# Node_Schematic_V2.net
KiCad netlist of a schematic drawn in Altium Designer
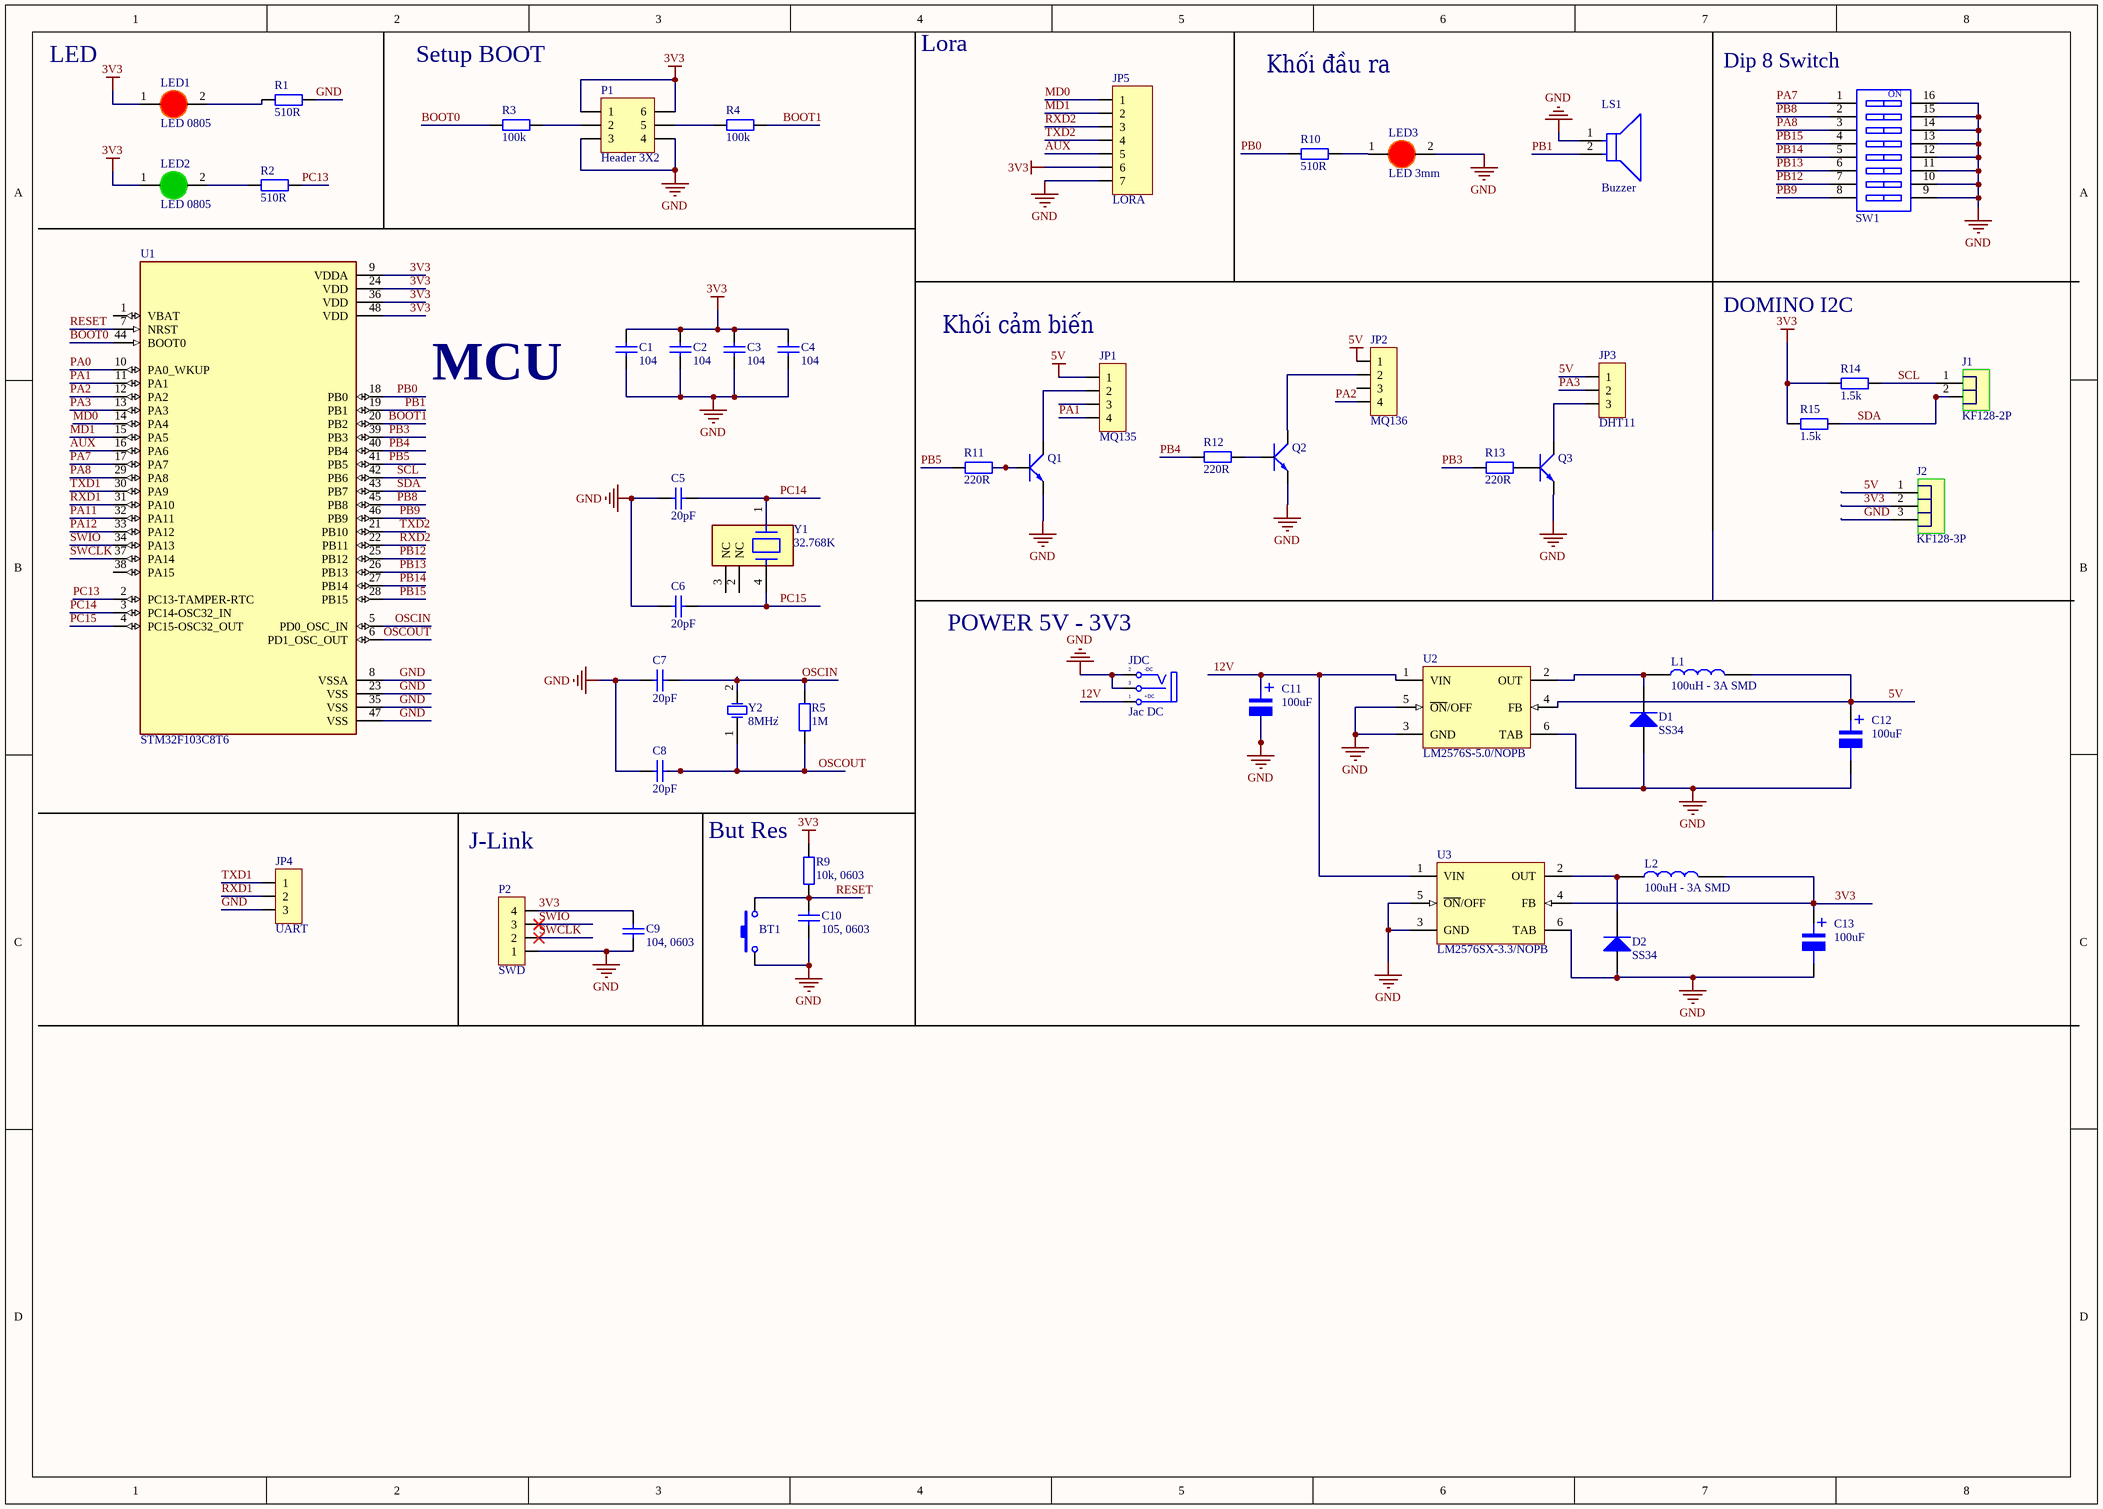
[diagram p0: Node_Schematic_V2.SchDoc]

(export (version "E")
  (design (tool "Eeschema 10.0.6"))
  (components
    (comp (ref "BT1")
      (value "Nut Nhan 2 Chan SMD 3x6x2.5")
      (footprint "Nut Nhan 2 Chan SMD 3x6x2.5")
      (libsource (lib "Altium_Lib_by_KhueNguyenCreator") (part "Nut Nhan 2 Chan SMD 3x6x2.5"))
    )
    (comp (ref "C1")
      (value "104")
      (footprint "tu 0603")
      (description "Dán")
      (libsource (lib "Altium_Lib_by_KhueNguyenCreator") (part "Tu 0603 104 50V 10%"))
    )
    (comp (ref "C2")
      (value "104")
      (footprint "tu 0603")
      (description "Dán")
      (libsource (lib "Altium_Lib_by_KhueNguyenCreator") (part "Tu 0603 104 50V 10%"))
    )
    (comp (ref "C3")
      (value "104")
      (footprint "tu 0603")
      (description "Dán")
      (libsource (lib "Altium_Lib_by_KhueNguyenCreator") (part "Tu 0603 104 50V 10%"))
    )
    (comp (ref "C4")
      (value "104")
      (footprint "tu 0603")
      (description "Dán")
      (libsource (lib "Altium_Lib_by_KhueNguyenCreator") (part "Tu 0603 104 50V 10%"))
    )
    (comp (ref "C5")
      (value "20pF")
      (footprint "tu 0805")
      (description "Dán")
      (libsource (lib "Altium_Lib_by_KhueNguyenCreator") (part "Tu 0805 20pF 50V 10%"))
    )
    (comp (ref "C6")
      (value "20pF")
      (footprint "tu 0805")
      (description "Dán")
      (libsource (lib "Altium_Lib_by_KhueNguyenCreator") (part "Tu 0805 20pF 50V 10%"))
    )
    (comp (ref "C7")
      (value "20pF")
      (footprint "tu 0805")
      (description "Dán")
      (libsource (lib "Altium_Lib_by_KhueNguyenCreator") (part "Tu 0805 20pF 50V 10%"))
    )
    (comp (ref "C8")
      (value "20pF")
      (footprint "tu 0805")
      (description "Dán")
      (libsource (lib "Altium_Lib_by_KhueNguyenCreator") (part "Tu 0805 20pF 50V 10%"))
    )
    (comp (ref "C9")
      (value "104, 0603")
      (footprint "tu 0603")
      (description "Dán")
      (libsource (lib "Altium_Lib_by_KhueNguyenCreator") (part "Tu 0603 104 50V 10%"))
    )
    (comp (ref "C10")
      (value "105, 0603")
      (footprint "tu 0603")
      (description "Dán")
      (libsource (lib "Altium_Lib_by_KhueNguyenCreator") (part "Tu 0603 105 16V 20%"))
    )
    (comp (ref "C11")
      (value "100uF")
      (footprint "tu nhom 8 (f)")
      (description "Dán")
      (libsource (lib "Altium_Lib_by_KhueNguyenCreator") (part "Tu Nhom 100uF 50V"))
    )
    (comp (ref "C12")
      (value "100uF")
      (footprint "tu nhom 8 (f)")
      (description "Dán")
      (libsource (lib "Altium_Lib_by_KhueNguyenCreator") (part "Tu Nhom 100uF 50V"))
    )
    (comp (ref "C13")
      (value "100uF")
      (footprint "tu nhom 8 (f)")
      (description "Dán")
      (libsource (lib "Altium_Lib_by_KhueNguyenCreator") (part "Tu Nhom 100uF 50V"))
    )
    (comp (ref "D1")
      (value "SS34")
      (footprint "DIODE SMA")
      (description "Dán")
      (libsource (lib "Altium_Lib_by_KhueNguyenCreator") (part "Diode SS34 ( 1N5822 )"))
    )
    (comp (ref "D2")
      (value "SS34")
      (footprint "DIODE SMA")
      (description "Dán")
      (libsource (lib "Altium_Lib_by_KhueNguyenCreator") (part "Diode SS34 ( 1N5822 )"))
    )
    (comp (ref "J1")
      (value "KF128-2P")
      (footprint "KF128-5.08-2P")
      (libsource (lib "KF128") (part "KF128-2P"))
    )
    (comp (ref "J2")
      (value "KF128-3P")
      (footprint "KF128-5.08-3P")
      (libsource (lib "KF128") (part "KF128-3P"))
    )
    (comp (ref "JDC")
      (value "Jac DC")
      (footprint "DC-IN")
      (description "Jac DC input")
      (libsource (lib "syhaunguyen") (part "DCIN"))
    )
    (comp (ref "JP1")
      (value "MQ135")
      (footprint "JP 1x4 CT")
      (description "Cắm")
      (libsource (lib "Altium_Lib_by_KhueNguyenCreator") (part "JP 1x4 2.54 Cai Thang"))
    )
    (comp (ref "JP2")
      (value "MQ136")
      (footprint "JP 1x4 CT")
      (description "Cắm")
      (libsource (lib "Altium_Lib_by_KhueNguyenCreator") (part "JP 1x4 2.54 Cai Thang"))
    )
    (comp (ref "JP3")
      (value "DHT11")
      (footprint "JP 1x3 CT")
      (description "Cắm")
      (libsource (lib "Altium_Lib_by_KhueNguyenCreator") (part "JP 1x3 2.54 Cai Thang"))
    )
    (comp (ref "JP4")
      (value "UART")
      (footprint "JP 1x3 DT")
      (description "Cắm")
      (libsource (lib "Altium_Lib_by_KhueNguyenCreator") (part "JP 1x3 2.54 Duc Thang"))
    )
    (comp (ref "JP5")
      (value "LORA")
      (footprint "JP 1x7 CT")
      (description "Cắm")
      (libsource (lib "Altium_Lib_by_KhueNguyenCreator") (part "JP 1x7 2.54 Cai Thang"))
    )
    (comp (ref "L1")
      (value "100uH - 3A SMD")
      (footprint "Cuon Cam 12x12x10")
      (description "Dán")
      (libsource (lib "Altium_Lib_by_KhueNguyenCreator") (part "CUON CAM 100uH SMD"))
    )
    (comp (ref "L2")
      (value "100uH - 3A SMD")
      (footprint "Cuon Cam 12x12x10")
      (description "Dán")
      (libsource (lib "Altium_Lib_by_KhueNguyenCreator") (part "CUON CAM 100uH SMD"))
    )
    (comp (ref "LED1")
      (value "LED 0805")
      (footprint "LED-0805-Red")
      (description "Dán")
      (libsource (lib "Altium_Lib_by_KhueNguyenCreator") (part "LED 0805 Do"))
    )
    (comp (ref "LED2")
      (value "LED 0805")
      (footprint "LED-0805-Green")
      (description "Dán")
      (libsource (lib "Altium_Lib_by_KhueNguyenCreator") (part "LED 0805 Xanh La"))
    )
    (comp (ref "LED3")
      (value "LED 3mm")
      (footprint "LED-3MM-RED")
      (description "Cắm")
      (libsource (lib "Altium_Lib_by_KhueNguyenCreator") (part "LED 3mm Do"))
    )
    (comp (ref "LS1")
      (value "Buzzer")
      (footprint "FP-MCKPX-G1203A-K4056-MFG")
      (description "MAGNETIC BUZZER AND TRANSDUCER - More Details")
      (fields
        (field (name "MANUFACTURER PART NUMBER") "MCKPX-G1203A-K4056")
        (field (name "MANUFACTURER") "Multicomp Pro")
      )
      (libsource (lib "Altium Content Vault") (part "1973c4b650225fd2ddacaff6b763965"))
    )
    (comp (ref "P1")
      (value "Header 3X2")
      (footprint "JP 2x3 DT")
      (description "Cắm")
      (libsource (lib "Altium_Lib_by_KhueNguyenCreator") (part "JP 2x3 2.54 Duc Thang"))
    )
    (comp (ref "P2")
      (value "SWD")
      (footprint "JP 1x4 DT")
      (description "Cắm")
      (libsource (lib "Altium_Lib_by_KhueNguyenCreator") (part "JP 1x4 2.54 Duc Thang"))
    )
    (comp (ref "Q1")
      (value "?")
      (footprint "TO92")
      (description "NPN transistor EBC")
      (libsource (lib "Altium_Lib_by_KhueNguyenCreator") (part "Trans 2N3904"))
    )
    (comp (ref "Q2")
      (value "?")
      (footprint "TO92")
      (description "NPN transistor EBC")
      (libsource (lib "Altium_Lib_by_KhueNguyenCreator") (part "Trans 2N3904"))
    )
    (comp (ref "Q3")
      (value "?")
      (footprint "TO92")
      (description "NPN transistor EBC")
      (libsource (lib "Altium_Lib_by_KhueNguyenCreator") (part "Trans 2N3904"))
    )
    (comp (ref "R1")
      (value "510R")
      (footprint "tro smd 0603")
      (description "Dán")
      (libsource (lib "Altium_Lib_by_KhueNguyenCreator") (part "Tro 0603 5% 510R"))
    )
    (comp (ref "R2")
      (value "510R")
      (footprint "tro smd 0603")
      (description "Dán")
      (libsource (lib "Altium_Lib_by_KhueNguyenCreator") (part "Tro 0603 5% 510R"))
    )
    (comp (ref "R3")
      (value "100k")
      (footprint "tro smd 0603")
      (description "Dán")
      (libsource (lib "Altium_Lib_by_KhueNguyenCreator") (part "Tro 0603 5% 100k"))
    )
    (comp (ref "R4")
      (value "100k")
      (footprint "tro smd 0603")
      (description "Dán")
      (libsource (lib "Altium_Lib_by_KhueNguyenCreator") (part "Tro 0603 5% 100k"))
    )
    (comp (ref "R5")
      (value "1M")
      (footprint "tro smd 0603")
      (description "Dán")
      (libsource (lib "Altium_Lib_by_KhueNguyenCreator") (part "Tro 0603 5% 1M"))
    )
    (comp (ref "R9")
      (value "10k, 0603")
      (footprint "tro smd 0603")
      (description "Dán")
      (libsource (lib "Altium_Lib_by_KhueNguyenCreator") (part "Tro 0603 1% 10k"))
    )
    (comp (ref "R10")
      (value "510R")
      (footprint "tro smd 0603")
      (description "Dán")
      (libsource (lib "Altium_Lib_by_KhueNguyenCreator") (part "Tro 0603 5% 510R"))
    )
    (comp (ref "R11")
      (value "220R")
      (footprint "tro smd 0603")
      (description "Dán")
      (libsource (lib "Altium_Lib_by_KhueNguyenCreator") (part "Tro 0603 5% 220R"))
    )
    (comp (ref "R12")
      (value "220R")
      (footprint "tro smd 0603")
      (description "Dán")
      (libsource (lib "Altium_Lib_by_KhueNguyenCreator") (part "Tro 0603 5% 220R"))
    )
    (comp (ref "R13")
      (value "220R")
      (footprint "tro smd 0603")
      (description "Dán")
      (libsource (lib "Altium_Lib_by_KhueNguyenCreator") (part "Tro 0603 5% 220R"))
    )
    (comp (ref "R14")
      (value "1.5k")
      (footprint "tro smd 0603")
      (description "Dán")
      (libsource (lib "Altium_Lib_by_KhueNguyenCreator") (part "Tro 0603 5% 1.5k"))
    )
    (comp (ref "R15")
      (value "1.5k")
      (footprint "tro smd 0603")
      (description "Dán")
      (libsource (lib "Altium_Lib_by_KhueNguyenCreator") (part "Tro 0603 5% 1.5k"))
    )
    (comp (ref "SW1")
      (value "418117270908")
      (footprint "418117270908")
      (description "WS-DITV Compact THT Dip Switch, Raised Actuator, pitch 2.54mm, 8p")
      (fields (field (name "MANUFACTURER") "Wurth Elektronik"))
      (libsource (lib "Dip8Switch") (part "418117270908"))
    )
    (comp (ref "U1")
      (value "STM32F103C8T6")
      (footprint "QFP50P900X900X160-48N")
      (description "ARM® Cortex®-M3 STM32F1 Microcontroller IC 32-Bit 72MHz 64KB (64K x 8) FLASH 48-LQFP (7x7)")
      (fields (field (name "MF") "STMicroelectronics"))
      (libsource (lib "STM32F103C8T6") (part "STM32F103C8T6"))
    )
    (comp (ref "U2")
      (value "LM2576S-5.0/NOPB")
      (footprint "KTT0005B_N")
      (description "SIMPLE SWITCHER® 3A Step-Down Voltage Regulator, 5-pin TO-263, Pb-Free")
      (fields (field (name "MANUFACTURER") "Texas Instruments"))
      (libsource (lib "LM2576S5NOPB") (part "CMP-0069-00114-3"))
    )
    (comp (ref "U3")
      (value "LM2576SX-3.3/NOPB")
      (footprint "KTT0005B_L")
      (description "SIMPLE SWITCHER® 3A Step-Down Voltage Regulator, 5-pin TO-263, Pb-Free")
      (fields (field (name "MANUFACTURER") "Texas Instruments"))
      (libsource (lib "Altium Content Vault") (part "PM-REG-LM2575HVS-12"))
    )
    (comp (ref "Y1")
      (value "32.768K")
      (footprint "FP-ABS25-MFG")
      (description "CRYSTAL 32.7680KHZ 12.5PF SMD")
      (fields (field (name "TOLERANCE") "20ppm"))
      (libsource (lib "thachanh_36,768k") (part "CMP-2000-05037-2"))
    )
    (comp (ref "Y2")
      (value "8MHz")
      (footprint "ABRA-ABLS-14.7456MHZ-B2-T_V")
      (description "Low Profile Crystal, 8.0 MHz, +/- 30 ppm, -20 to 70 degC, 2-Pin SMD, RoHS, Tape and Reel")
      (fields (field (name "MANUFACTURER") "ABRACON") (field (name "TOLERANCE") "30PPM"))
      (libsource (lib "thachanh_8M") (part "CMP-2000-05726-1"))
    )
  )
  (nets
    (net (code "1") (name "/12V") (class "Default")
      (node (ref "C11") (pin "1") (pinfunction "1_1") (pintype "passive"))
      (node (ref "JDC") (pin "1") (pinfunction "T_1") (pintype "passive"))
      (node (ref "U2") (pin "1") (pinfunction "VIN_1") (pintype "power_in"))
      (node (ref "U3") (pin "1") (pinfunction "VIN_1") (pintype "power_in"))
    )
    (net (code "2") (name "/AUX") (class "Default")
      (node (ref "JP5") (pin "5") (pinfunction "5_5") (pintype "passive"))
      (node (ref "U1") (pin "16") (pinfunction "PA6_16") (pintype "bidirectional"))
    )
    (net (code "3") (name "/BOOT0") (class "Default")
      (node (ref "R3") (pin "1") (pinfunction "1_1") (pintype "passive"))
      (node (ref "U1") (pin "44") (pinfunction "BOOT0_44") (pintype "input"))
    )
    (net (code "4") (name "/BOOT1") (class "Default")
      (node (ref "R4") (pin "2") (pinfunction "2_2") (pintype "passive"))
      (node (ref "U1") (pin "20") (pinfunction "PB2_20") (pintype "bidirectional"))
    )
    (net (code "5") (name "/MD0") (class "Default")
      (node (ref "JP5") (pin "1") (pinfunction "1_1") (pintype "passive"))
      (node (ref "U1") (pin "14") (pinfunction "PA4_14") (pintype "bidirectional"))
    )
    (net (code "6") (name "/MD1") (class "Default")
      (node (ref "JP5") (pin "2") (pinfunction "2_2") (pintype "passive"))
      (node (ref "U1") (pin "15") (pinfunction "PA5_15") (pintype "bidirectional"))
    )
    (net (code "7") (name "/OSCIN") (class "Default")
      (node (ref "C7") (pin "1") (pinfunction "1_1") (pintype "passive"))
      (node (ref "R5") (pin "2") (pinfunction "2_2") (pintype "passive"))
      (node (ref "U1") (pin "5") (pinfunction "PD0_OSC_IN_5") (pintype "bidirectional"))
      (node (ref "Y2") (pin "2") (pinfunction "X2_2") (pintype "passive"))
    )
    (net (code "8") (name "/OSCOUT") (class "Default")
      (node (ref "C8") (pin "1") (pinfunction "1_1") (pintype "passive"))
      (node (ref "R5") (pin "1") (pinfunction "1_1") (pintype "passive"))
      (node (ref "U1") (pin "6") (pinfunction "PD1_OSC_OUT_6") (pintype "bidirectional"))
      (node (ref "Y2") (pin "1") (pinfunction "X1_1") (pintype "passive"))
    )
    (net (code "9") (name "/PA0") (class "Default")
      (node (ref "U1") (pin "10") (pinfunction "PA0_WKUP_10") (pintype "bidirectional"))
    )
    (net (code "10") (name "/PA1") (class "Default")
      (node (ref "JP1") (pin "4") (pinfunction "4_4") (pintype "passive"))
      (node (ref "U1") (pin "11") (pinfunction "PA1_11") (pintype "bidirectional"))
    )
    (net (code "11") (name "/PA2") (class "Default")
      (node (ref "JP2") (pin "4") (pinfunction "4_4") (pintype "passive"))
      (node (ref "U1") (pin "12") (pinfunction "PA2_12") (pintype "bidirectional"))
    )
    (net (code "12") (name "/PA3") (class "Default")
      (node (ref "JP3") (pin "2") (pinfunction "2_2") (pintype "passive"))
      (node (ref "U1") (pin "13") (pinfunction "PA3_13") (pintype "bidirectional"))
    )
    (net (code "13") (name "/PA7") (class "Default")
      (node (ref "SW1") (pin "1") (pinfunction "1_1") (pintype "passive"))
      (node (ref "U1") (pin "17") (pinfunction "PA7_17") (pintype "bidirectional"))
    )
    (net (code "14") (name "/PA8") (class "Default")
      (node (ref "SW1") (pin "3") (pinfunction "3_3") (pintype "passive"))
      (node (ref "U1") (pin "29") (pinfunction "PA8_29") (pintype "bidirectional"))
    )
    (net (code "15") (name "/PA11") (class "Default")
      (node (ref "U1") (pin "32") (pinfunction "PA11_32") (pintype "bidirectional"))
    )
    (net (code "16") (name "/PA12") (class "Default")
      (node (ref "U1") (pin "33") (pinfunction "PA12_33") (pintype "bidirectional"))
    )
    (net (code "17") (name "/PB0") (class "Default")
      (node (ref "R10") (pin "1") (pinfunction "1_1") (pintype "passive"))
      (node (ref "U1") (pin "18") (pinfunction "PB0_18") (pintype "bidirectional"))
    )
    (net (code "18") (name "/PB1") (class "Default")
      (node (ref "LS1") (pin "2") (pinfunction "A_2") (pintype "passive"))
      (node (ref "U1") (pin "19") (pinfunction "PB1_19") (pintype "bidirectional"))
    )
    (net (code "19") (name "/PB3") (class "Default")
      (node (ref "R13") (pin "1") (pinfunction "1_1") (pintype "passive"))
      (node (ref "U1") (pin "39") (pinfunction "PB3_39") (pintype "bidirectional"))
    )
    (net (code "20") (name "/PB4") (class "Default")
      (node (ref "R12") (pin "1") (pinfunction "1_1") (pintype "passive"))
      (node (ref "U1") (pin "40") (pinfunction "PB4_40") (pintype "bidirectional"))
    )
    (net (code "21") (name "/PB5") (class "Default")
      (node (ref "R11") (pin "1") (pinfunction "1_1") (pintype "passive"))
      (node (ref "U1") (pin "41") (pinfunction "PB5_41") (pintype "bidirectional"))
    )
    (net (code "22") (name "/PB8") (class "Default")
      (node (ref "SW1") (pin "2") (pinfunction "2_2") (pintype "passive"))
      (node (ref "U1") (pin "45") (pinfunction "PB8_45") (pintype "bidirectional"))
    )
    (net (code "23") (name "/PB9") (class "Default")
      (node (ref "SW1") (pin "8") (pinfunction "8_8") (pintype "passive"))
      (node (ref "U1") (pin "46") (pinfunction "PB9_46") (pintype "bidirectional"))
    )
    (net (code "24") (name "/PB12") (class "Default")
      (node (ref "SW1") (pin "7") (pinfunction "7_7") (pintype "passive"))
      (node (ref "U1") (pin "25") (pinfunction "PB12_25") (pintype "bidirectional"))
    )
    (net (code "25") (name "/PB13") (class "Default")
      (node (ref "SW1") (pin "6") (pinfunction "6_6") (pintype "passive"))
      (node (ref "U1") (pin "26") (pinfunction "PB13_26") (pintype "bidirectional"))
    )
    (net (code "26") (name "/PB14") (class "Default")
      (node (ref "SW1") (pin "5") (pinfunction "5_5") (pintype "passive"))
      (node (ref "U1") (pin "27") (pinfunction "PB14_27") (pintype "bidirectional"))
    )
    (net (code "27") (name "/PB15") (class "Default")
      (node (ref "SW1") (pin "4") (pinfunction "4_4") (pintype "passive"))
      (node (ref "U1") (pin "28") (pinfunction "PB15_28") (pintype "bidirectional"))
    )
    (net (code "28") (name "/PC13") (class "Default")
      (node (ref "R2") (pin "2") (pinfunction "2_2") (pintype "passive"))
      (node (ref "U1") (pin "2") (pinfunction "PC13-TAMPER-RTC_2") (pintype "bidirectional"))
    )
    (net (code "29") (name "/PC14") (class "Default")
      (node (ref "C5") (pin "1") (pinfunction "1_1") (pintype "passive"))
      (node (ref "U1") (pin "3") (pinfunction "PC14-OSC32_IN_3") (pintype "bidirectional"))
      (node (ref "Y1") (pin "1") (pinfunction "1_1") (pintype "passive"))
    )
    (net (code "30") (name "/PC15") (class "Default")
      (node (ref "C6") (pin "1") (pinfunction "1_1") (pintype "passive"))
      (node (ref "U1") (pin "4") (pinfunction "PC15-OSC32_OUT_4") (pintype "bidirectional"))
      (node (ref "Y1") (pin "4") (pinfunction "4_4") (pintype "passive"))
    )
    (net (code "31") (name "/RESET") (class "Default")
      (node (ref "BT1") (pin "2") (pinfunction "2_2") (pintype "passive"))
      (node (ref "C10") (pin "1") (pinfunction "1_1") (pintype "passive"))
      (node (ref "R9") (pin "1") (pinfunction "1_1") (pintype "passive"))
      (node (ref "U1") (pin "7") (pinfunction "NRST_7") (pintype "input"))
    )
    (net (code "32") (name "/RXD1") (class "Default")
      (node (ref "JP4") (pin "2") (pinfunction "2_2") (pintype "passive"))
      (node (ref "U1") (pin "31") (pinfunction "PA10_31") (pintype "bidirectional"))
    )
    (net (code "33") (name "/RXD2") (class "Default")
      (node (ref "JP5") (pin "3") (pinfunction "3_3") (pintype "passive"))
      (node (ref "U1") (pin "22") (pinfunction "PB11_22") (pintype "bidirectional"))
    )
    (net (code "34") (name "/SCL") (class "Default")
      (node (ref "J1") (pin "1") (pinfunction "1_1") (pintype "passive"))
      (node (ref "R14") (pin "2") (pinfunction "2_2") (pintype "passive"))
      (node (ref "U1") (pin "42") (pinfunction "PB6_42") (pintype "bidirectional"))
    )
    (net (code "35") (name "/SDA") (class "Default")
      (node (ref "J1") (pin "2") (pinfunction "2_2") (pintype "passive"))
      (node (ref "R15") (pin "2") (pinfunction "2_2") (pintype "passive"))
      (node (ref "U1") (pin "43") (pinfunction "PB7_43") (pintype "bidirectional"))
    )
    (net (code "36") (name "/SWCLK") (class "Default")
      (node (ref "P2") (pin "2") (pinfunction "2_2") (pintype "passive"))
      (node (ref "U1") (pin "37") (pinfunction "PA14_37") (pintype "bidirectional"))
    )
    (net (code "37") (name "/SWIO") (class "Default")
      (node (ref "P2") (pin "3") (pinfunction "3_3") (pintype "passive"))
      (node (ref "U1") (pin "34") (pinfunction "PA13_34") (pintype "bidirectional"))
    )
    (net (code "38") (name "/TXD1") (class "Default")
      (node (ref "JP4") (pin "1") (pinfunction "1_1") (pintype "passive"))
      (node (ref "U1") (pin "30") (pinfunction "PA9_30") (pintype "bidirectional"))
    )
    (net (code "39") (name "/TXD2") (class "Default")
      (node (ref "JP5") (pin "4") (pinfunction "4_4") (pintype "passive"))
      (node (ref "U1") (pin "21") (pinfunction "PB10_21") (pintype "bidirectional"))
    )
    (net (code "40") (name "3V3") (class "Default")
      (node (ref "C1") (pin "1") (pinfunction "1_1") (pintype "passive"))
      (node (ref "C13") (pin "1") (pinfunction "1_1") (pintype "passive"))
      (node (ref "C2") (pin "1") (pinfunction "1_1") (pintype "passive"))
      (node (ref "C3") (pin "1") (pinfunction "1_1") (pintype "passive"))
      (node (ref "C4") (pin "1") (pinfunction "1_1") (pintype "passive"))
      (node (ref "C9") (pin "1") (pinfunction "1_1") (pintype "passive"))
      (node (ref "J2") (pin "2") (pinfunction "2_2") (pintype "passive"))
      (node (ref "JP5") (pin "6") (pinfunction "6_6") (pintype "passive"))
      (node (ref "L2") (pin "2") (pinfunction "2_2") (pintype "passive"))
      (node (ref "LED1") (pin "1") (pinfunction "A_1") (pintype "passive"))
      (node (ref "LED2") (pin "1") (pinfunction "A_1") (pintype "passive"))
      (node (ref "P1") (pin "1") (pinfunction "1_1") (pintype "passive"))
      (node (ref "P1") (pin "6") (pinfunction "6_6") (pintype "passive"))
      (node (ref "P2") (pin "4") (pinfunction "4_4") (pintype "passive"))
      (node (ref "R14") (pin "1") (pinfunction "1_1") (pintype "passive"))
      (node (ref "R15") (pin "1") (pinfunction "1_1") (pintype "passive"))
      (node (ref "R9") (pin "2") (pinfunction "2_2") (pintype "passive"))
      (node (ref "U1") (pin "24") (pinfunction "VDD_24") (pintype "power_in"))
      (node (ref "U1") (pin "36") (pinfunction "VDD_36") (pintype "power_in"))
      (node (ref "U1") (pin "48") (pinfunction "VDD_48") (pintype "power_in"))
      (node (ref "U1") (pin "9") (pinfunction "VDDA_9") (pintype "power_in"))
      (node (ref "U3") (pin "4") (pinfunction "FB_4") (pintype "input"))
    )
    (net (code "41") (name "5V") (class "Default")
      (node (ref "C12") (pin "1") (pinfunction "1_1") (pintype "passive"))
      (node (ref "J2") (pin "1") (pinfunction "1_1") (pintype "passive"))
      (node (ref "JP1") (pin "1") (pinfunction "1_1") (pintype "passive"))
      (node (ref "JP2") (pin "1") (pinfunction "1_1") (pintype "passive"))
      (node (ref "JP3") (pin "1") (pinfunction "1_1") (pintype "passive"))
      (node (ref "L1") (pin "2") (pinfunction "2_2") (pintype "passive"))
      (node (ref "U2") (pin "4") (pinfunction "FB_4") (pintype "input"))
    )
    (net (code "42") (name "GND") (class "Default")
      (node (ref "BT1") (pin "1") (pinfunction "1_1") (pintype "passive"))
      (node (ref "C1") (pin "2") (pinfunction "2_2") (pintype "passive"))
      (node (ref "C10") (pin "2") (pinfunction "2_2") (pintype "passive"))
      (node (ref "C11") (pin "2") (pinfunction "2_2") (pintype "passive"))
      (node (ref "C12") (pin "2") (pinfunction "2_2") (pintype "passive"))
      (node (ref "C13") (pin "2") (pinfunction "2_2") (pintype "passive"))
      (node (ref "C2") (pin "2") (pinfunction "2_2") (pintype "passive"))
      (node (ref "C3") (pin "2") (pinfunction "2_2") (pintype "passive"))
      (node (ref "C4") (pin "2") (pinfunction "2_2") (pintype "passive"))
      (node (ref "C5") (pin "2") (pinfunction "2_2") (pintype "passive"))
      (node (ref "C6") (pin "2") (pinfunction "2_2") (pintype "passive"))
      (node (ref "C7") (pin "2") (pinfunction "2_2") (pintype "passive"))
      (node (ref "C8") (pin "2") (pinfunction "2_2") (pintype "passive"))
      (node (ref "C9") (pin "2") (pinfunction "2_2") (pintype "passive"))
      (node (ref "D1") (pin "1") (pinfunction "A_1") (pintype "passive"))
      (node (ref "D2") (pin "1") (pinfunction "A_1") (pintype "passive"))
      (node (ref "J2") (pin "3") (pinfunction "3_3") (pintype "passive"))
      (node (ref "JDC") (pin "2") (pinfunction "TN_2") (pintype "passive"))
      (node (ref "JDC") (pin "3") (pinfunction "S_3") (pintype "power_in"))
      (node (ref "JP4") (pin "3") (pinfunction "3_3") (pintype "passive"))
      (node (ref "JP5") (pin "7") (pinfunction "7_7") (pintype "passive"))
      (node (ref "LED3") (pin "2") (pinfunction "K_2") (pintype "passive"))
      (node (ref "LS1") (pin "1") (pinfunction "C_1") (pintype "passive"))
      (node (ref "P1") (pin "3") (pinfunction "3_3") (pintype "passive"))
      (node (ref "P1") (pin "4") (pinfunction "4_4") (pintype "passive"))
      (node (ref "P2") (pin "1") (pinfunction "1_1") (pintype "passive"))
      (node (ref "Q1") (pin "1") (pinfunction "E_1") (pintype "passive"))
      (node (ref "Q2") (pin "1") (pinfunction "E_1") (pintype "passive"))
      (node (ref "Q3") (pin "1") (pinfunction "E_1") (pintype "passive"))
      (node (ref "R1") (pin "2") (pinfunction "2_2") (pintype "passive"))
      (node (ref "SW1") (pin "10") (pinfunction "10_10") (pintype "passive"))
      (node (ref "SW1") (pin "11") (pinfunction "11_11") (pintype "passive"))
      (node (ref "SW1") (pin "12") (pinfunction "12_12") (pintype "passive"))
      (node (ref "SW1") (pin "13") (pinfunction "13_13") (pintype "passive"))
      (node (ref "SW1") (pin "14") (pinfunction "14_14") (pintype "passive"))
      (node (ref "SW1") (pin "15") (pinfunction "15_15") (pintype "passive"))
      (node (ref "SW1") (pin "16") (pinfunction "16_16") (pintype "passive"))
      (node (ref "SW1") (pin "9") (pinfunction "9_9") (pintype "passive"))
      (node (ref "U1") (pin "23") (pinfunction "VSS_23") (pintype "power_in"))
      (node (ref "U1") (pin "35") (pinfunction "VSS_35") (pintype "power_in"))
      (node (ref "U1") (pin "47") (pinfunction "VSS_47") (pintype "power_in"))
      (node (ref "U1") (pin "8") (pinfunction "VSSA_8") (pintype "power_in"))
      (node (ref "U2") (pin "3") (pinfunction "GND_3") (pintype "power_in"))
      (node (ref "U2") (pin "5") (pinfunction "~{ON}/OFF_5") (pintype "input"))
      (node (ref "U2") (pin "6") (pinfunction "TAB_6") (pintype "power_in"))
      (node (ref "U3") (pin "3") (pinfunction "GND_3") (pintype "power_in"))
      (node (ref "U3") (pin "5") (pinfunction "~{ON}/OFF_5") (pintype "input"))
      (node (ref "U3") (pin "6") (pinfunction "TAB_6") (pintype "power_in"))
    )
    (net (code "43") (name "Net-(D1-K)") (class "Default")
      (node (ref "D1") (pin "2") (pinfunction "K_2") (pintype "passive"))
      (node (ref "L1") (pin "1") (pinfunction "1_1") (pintype "passive"))
      (node (ref "U2") (pin "2") (pinfunction "OUT_2") (pintype "power_in"))
    )
    (net (code "44") (name "Net-(D2-K)") (class "Default")
      (node (ref "D2") (pin "2") (pinfunction "K_2") (pintype "passive"))
      (node (ref "L2") (pin "1") (pinfunction "1_1") (pintype "passive"))
      (node (ref "U3") (pin "2") (pinfunction "OUT_2") (pintype "power_in"))
    )
    (net (code "45") (name "Net-(LED1-K)") (class "Default")
      (node (ref "LED1") (pin "2") (pinfunction "K_2") (pintype "passive"))
      (node (ref "R1") (pin "1") (pinfunction "1_1") (pintype "passive"))
    )
    (net (code "46") (name "Net-(LED2-K)") (class "Default")
      (node (ref "LED2") (pin "2") (pinfunction "K_2") (pintype "passive"))
      (node (ref "R2") (pin "1") (pinfunction "1_1") (pintype "passive"))
    )
    (net (code "47") (name "Net-(LED3-A)") (class "Default")
      (node (ref "LED3") (pin "1") (pinfunction "A_1") (pintype "passive"))
      (node (ref "R10") (pin "2") (pinfunction "2_2") (pintype "passive"))
    )
    (net (code "48") (name "Net-(P1-Pad2)") (class "Default")
      (node (ref "P1") (pin "2") (pinfunction "2_2") (pintype "passive"))
      (node (ref "R3") (pin "2") (pinfunction "2_2") (pintype "passive"))
    )
    (net (code "49") (name "Net-(P1-Pad5)") (class "Default")
      (node (ref "P1") (pin "5") (pinfunction "5_5") (pintype "passive"))
      (node (ref "R4") (pin "1") (pinfunction "1_1") (pintype "passive"))
    )
    (net (code "50") (name "Net-(Q1-B)") (class "Default")
      (node (ref "Q1") (pin "2") (pinfunction "B_2") (pintype "passive"))
      (node (ref "R11") (pin "2") (pinfunction "2_2") (pintype "passive"))
    )
    (net (code "51") (name "Net-(Q1-C)") (class "Default")
      (node (ref "JP1") (pin "2") (pinfunction "2_2") (pintype "passive"))
      (node (ref "Q1") (pin "3") (pinfunction "C_3") (pintype "passive"))
    )
    (net (code "52") (name "Net-(Q2-B)") (class "Default")
      (node (ref "Q2") (pin "2") (pinfunction "B_2") (pintype "passive"))
      (node (ref "R12") (pin "2") (pinfunction "2_2") (pintype "passive"))
    )
    (net (code "53") (name "Net-(Q2-C)") (class "Default")
      (node (ref "JP2") (pin "2") (pinfunction "2_2") (pintype "passive"))
      (node (ref "Q2") (pin "3") (pinfunction "C_3") (pintype "passive"))
    )
    (net (code "54") (name "Net-(Q3-B)") (class "Default")
      (node (ref "Q3") (pin "2") (pinfunction "B_2") (pintype "passive"))
      (node (ref "R13") (pin "2") (pinfunction "2_2") (pintype "passive"))
    )
    (net (code "55") (name "Net-(Q3-C)") (class "Default")
      (node (ref "JP3") (pin "3") (pinfunction "3_3") (pintype "passive"))
      (node (ref "Q3") (pin "3") (pinfunction "C_3") (pintype "passive"))
    )
    (net (code "56") (name "unconnected-(JP1-Pad3)") (class "Default")
      (node (ref "JP1") (pin "3") (pinfunction "3_3") (pintype "passive"))
    )
    (net (code "57") (name "unconnected-(JP2-Pad3)") (class "Default")
      (node (ref "JP2") (pin "3") (pinfunction "3_3") (pintype "passive"))
    )
    (net (code "58") (name "unconnected-(U1-PA15-Pad38)") (class "Default")
      (node (ref "U1") (pin "38") (pinfunction "PA15_38") (pintype "bidirectional"))
    )
    (net (code "59") (name "unconnected-(U1-VBAT-Pad1)") (class "Default")
      (node (ref "U1") (pin "1") (pinfunction "VBAT_1") (pintype "bidirectional"))
    )
    (net (code "60") (name "unconnected-(Y1-NC-Pad2)") (class "Default")
      (node (ref "Y1") (pin "2") (pinfunction "NC_2") (pintype "passive"))
    )
    (net (code "61") (name "unconnected-(Y1-NC-Pad3)") (class "Default")
      (node (ref "Y1") (pin "3") (pinfunction "NC_3") (pintype "passive"))
    )
  )
)
